# SCH_nfc_card_2023-10-30.net
KiCad netlist of a schematic drawn in EasyEDA
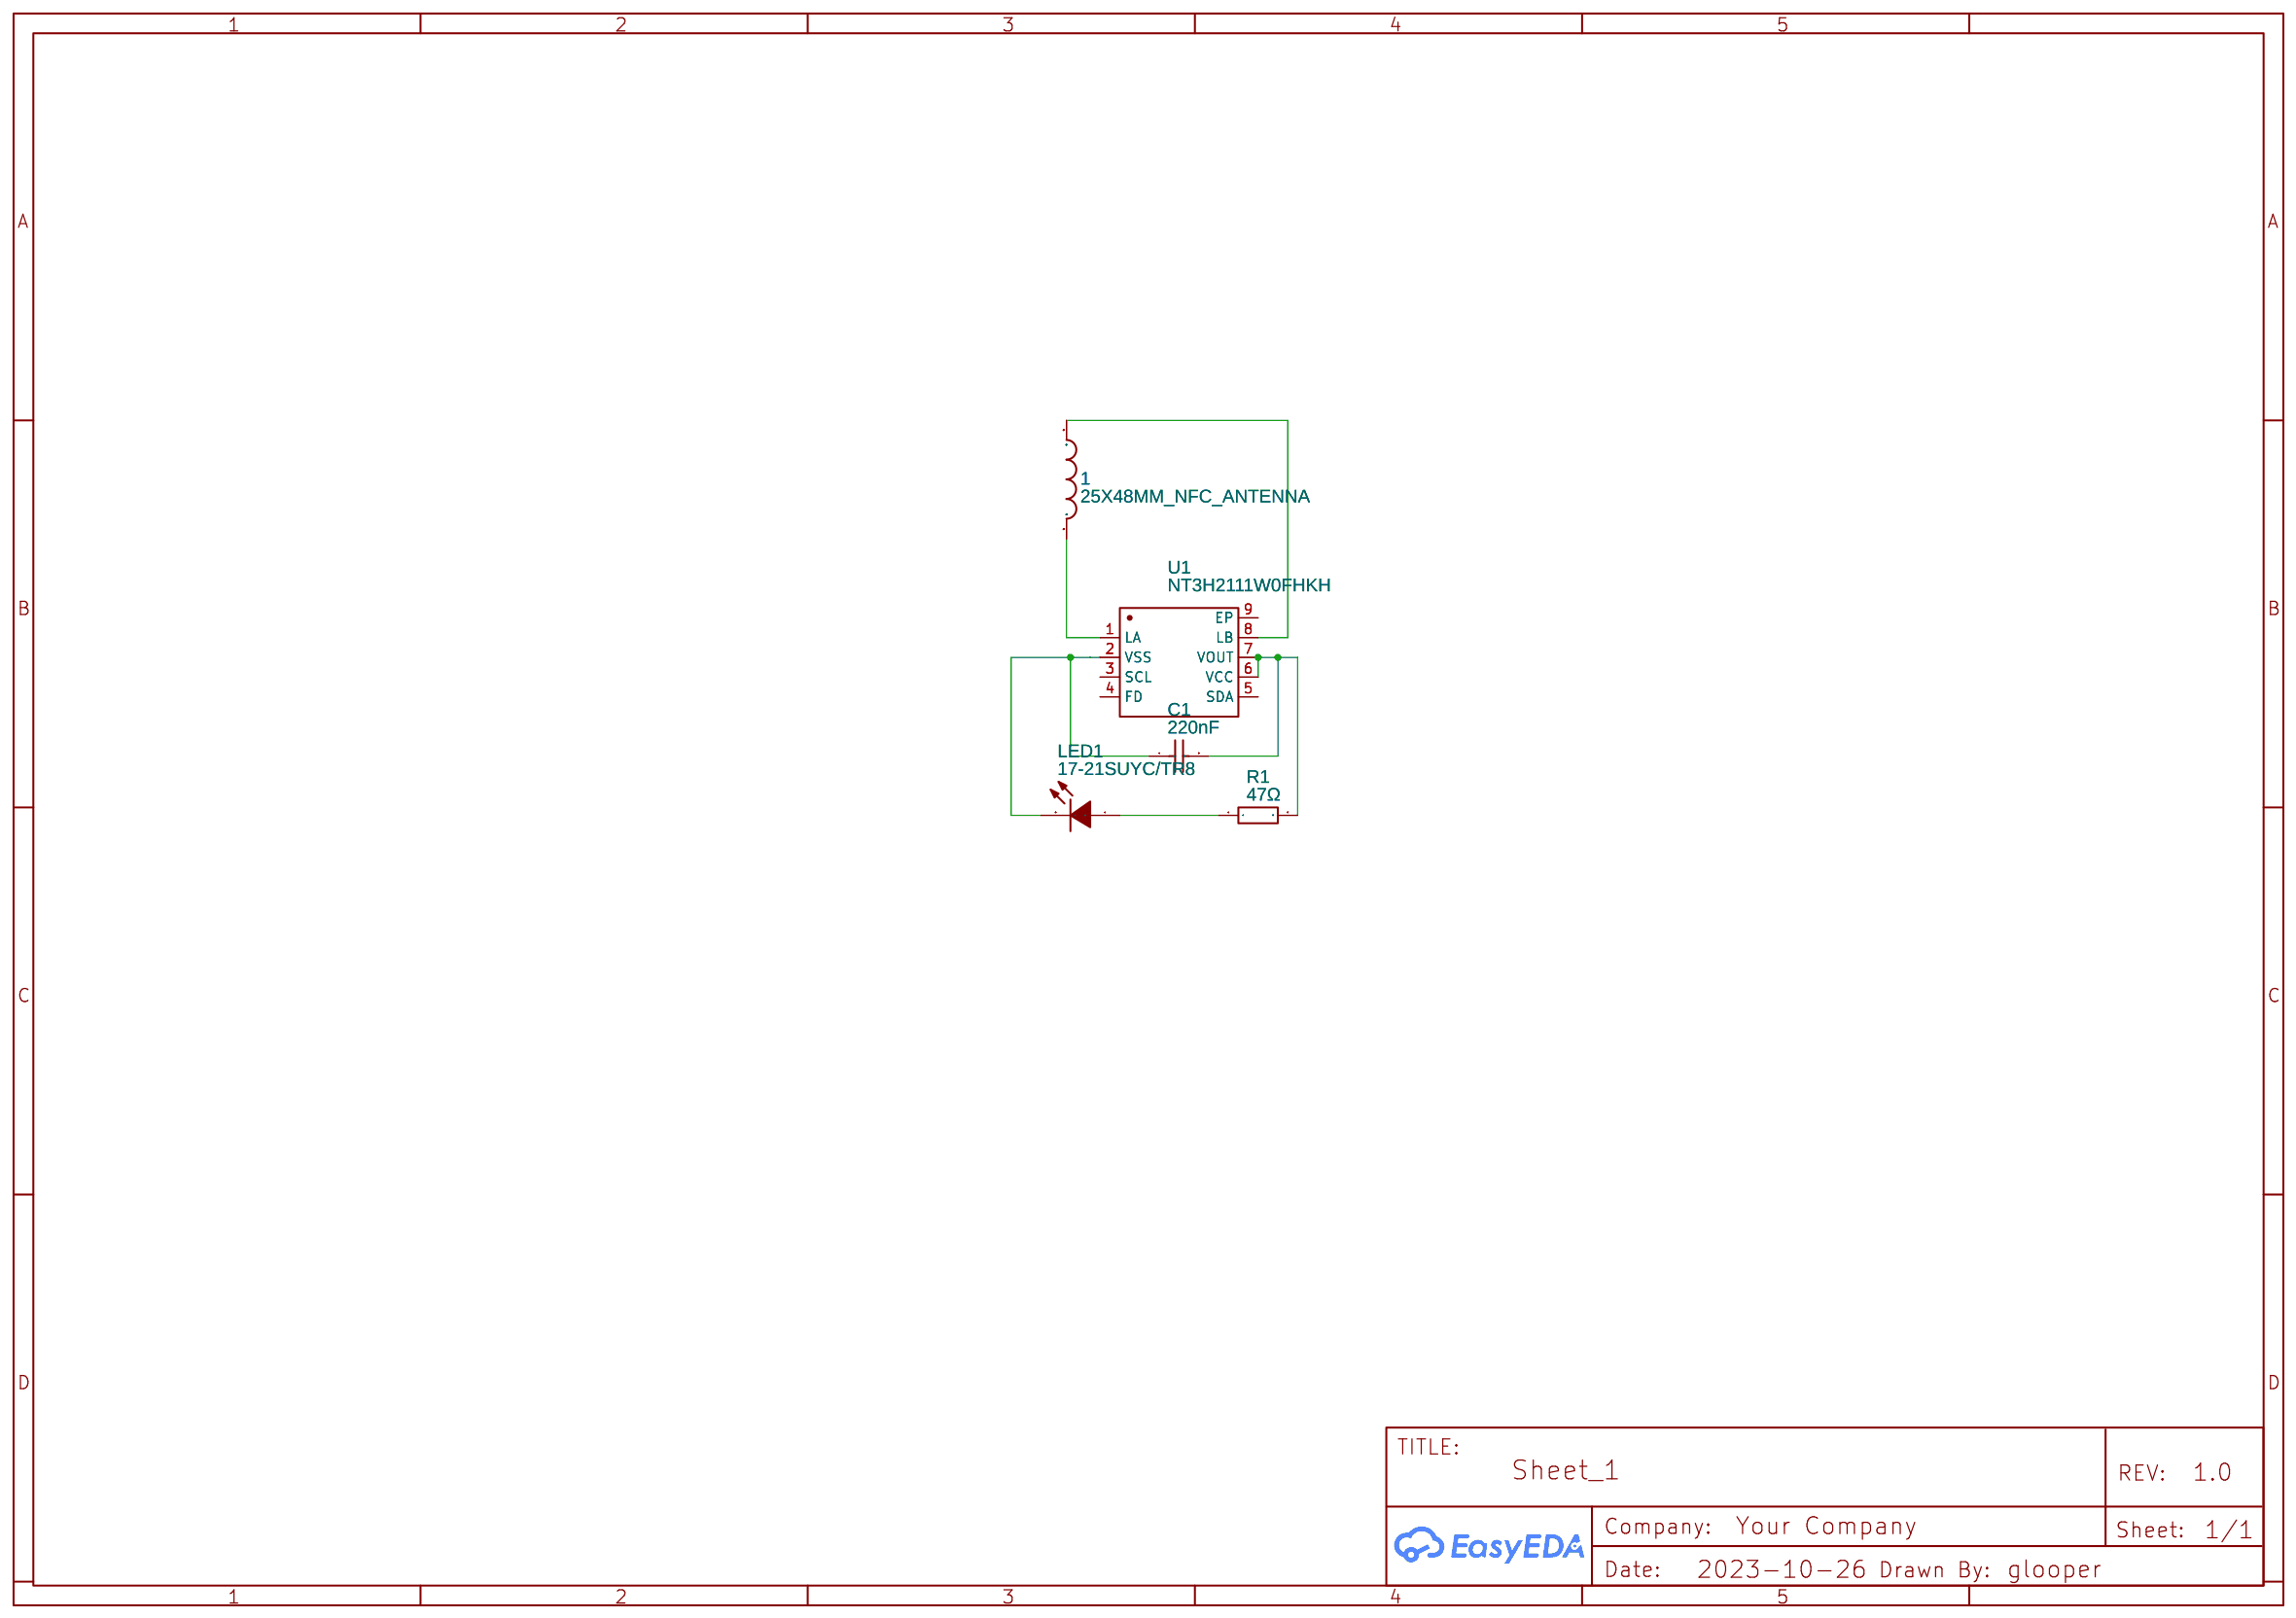
[diagram p0: schematic sheet]

(export (version "E")
  (design (tool "Eeschema 10.0.6"))
  (components
    (comp (ref "1") (value "25X48MM_NFC_ANTENNA") (libsource (lib "") (part "25X48MM_NFC_ANTENNA")))
    (comp (ref "C1")
      (value "220nF")
      (fields
        (field (name "Manufacturer Part") "CL10B224KA8NNNC")
        (field (name "Manufacturer") "SAMSUNG(三星)")
      )
      (libsource (lib "") (part "CL10B224KA8NNNC"))
    )
    (comp (ref "LED1")
      (value "17-21SUYC/TR8")
      (fields (field (name "Manufacturer Part") "KT-0805黄灯") (field (name "Manufacturer") "KENTO"))
      (libsource (lib "") (part "17-21SUYC/TR8"))
    )
    (comp (ref "R1")
      (value "47Ω")
      (fields
        (field (name "Manufacturer Part") "0603WAF470JT5E")
        (field (name "Manufacturer") "UNI-ROYAL(厚声)")
      )
      (libsource (lib "") (part "0603WAF470JT5E"))
    )
    (comp (ref "U1")
      (value "NT3H2111W0FHKH")
      (fields (field (name "Manufacturer") "NXP(恩智浦)"))
      (libsource (lib "") (part "NT3H2111W0FHKH"))
    )
  )
  (nets
    (net (code "1") (name "Net-(LED1-+)") (class "Default")
      (node (ref "LED1") (pin "1") (pinfunction "+_1") (pintype "unspecified"))
      (node (ref "R1") (pin "1") (pinfunction "1_1") (pintype "input"))
    )
    (net (code "2") (name "Net-(LED1--)") (class "Default")
      (node (ref "C1") (pin "1") (pinfunction "1_1") (pintype "input"))
      (node (ref "LED1") (pin "2") (pinfunction "-_2") (pintype "unspecified"))
      (node (ref "U1") (pin "2") (pinfunction "VSS_2") (pintype "unspecified"))
    )
    (net (code "3") (name "Net-(U1-LA)") (class "Default")
      (node (ref "1") (pin "P$2") (pinfunction "P$2_P$2") (pintype "bidirectional"))
      (node (ref "U1") (pin "1") (pinfunction "LA_1") (pintype "unspecified"))
    )
    (net (code "4") (name "Net-(U1-LB)") (class "Default")
      (node (ref "1") (pin "P$1") (pinfunction "P$1_P$1") (pintype "bidirectional"))
      (node (ref "U1") (pin "8") (pinfunction "LB_8") (pintype "unspecified"))
    )
    (net (code "5") (name "Net-(U1-VCC)") (class "Default")
      (node (ref "C1") (pin "2") (pinfunction "2_2") (pintype "input"))
      (node (ref "R1") (pin "2") (pinfunction "2_2") (pintype "input"))
      (node (ref "U1") (pin "6") (pinfunction "VCC_6") (pintype "unspecified"))
      (node (ref "U1") (pin "7") (pinfunction "VOUT_7") (pintype "unspecified"))
    )
    (net (code "6") (name "unconnected-(U1-EP-Pad9)") (class "Default")
      (node (ref "U1") (pin "9") (pinfunction "EP_9") (pintype "unspecified"))
    )
    (net (code "7") (name "unconnected-(U1-FD-Pad4)") (class "Default")
      (node (ref "U1") (pin "4") (pinfunction "FD_4") (pintype "unspecified"))
    )
    (net (code "8") (name "unconnected-(U1-SCL-Pad3)") (class "Default")
      (node (ref "U1") (pin "3") (pinfunction "SCL_3") (pintype "unspecified"))
    )
    (net (code "9") (name "unconnected-(U1-SDA-Pad5)") (class "Default")
      (node (ref "U1") (pin "5") (pinfunction "SDA_5") (pintype "unspecified"))
    )
  )
)
